# kl25_1.net
KiCad netlist of a schematic drawn in Altium Designer
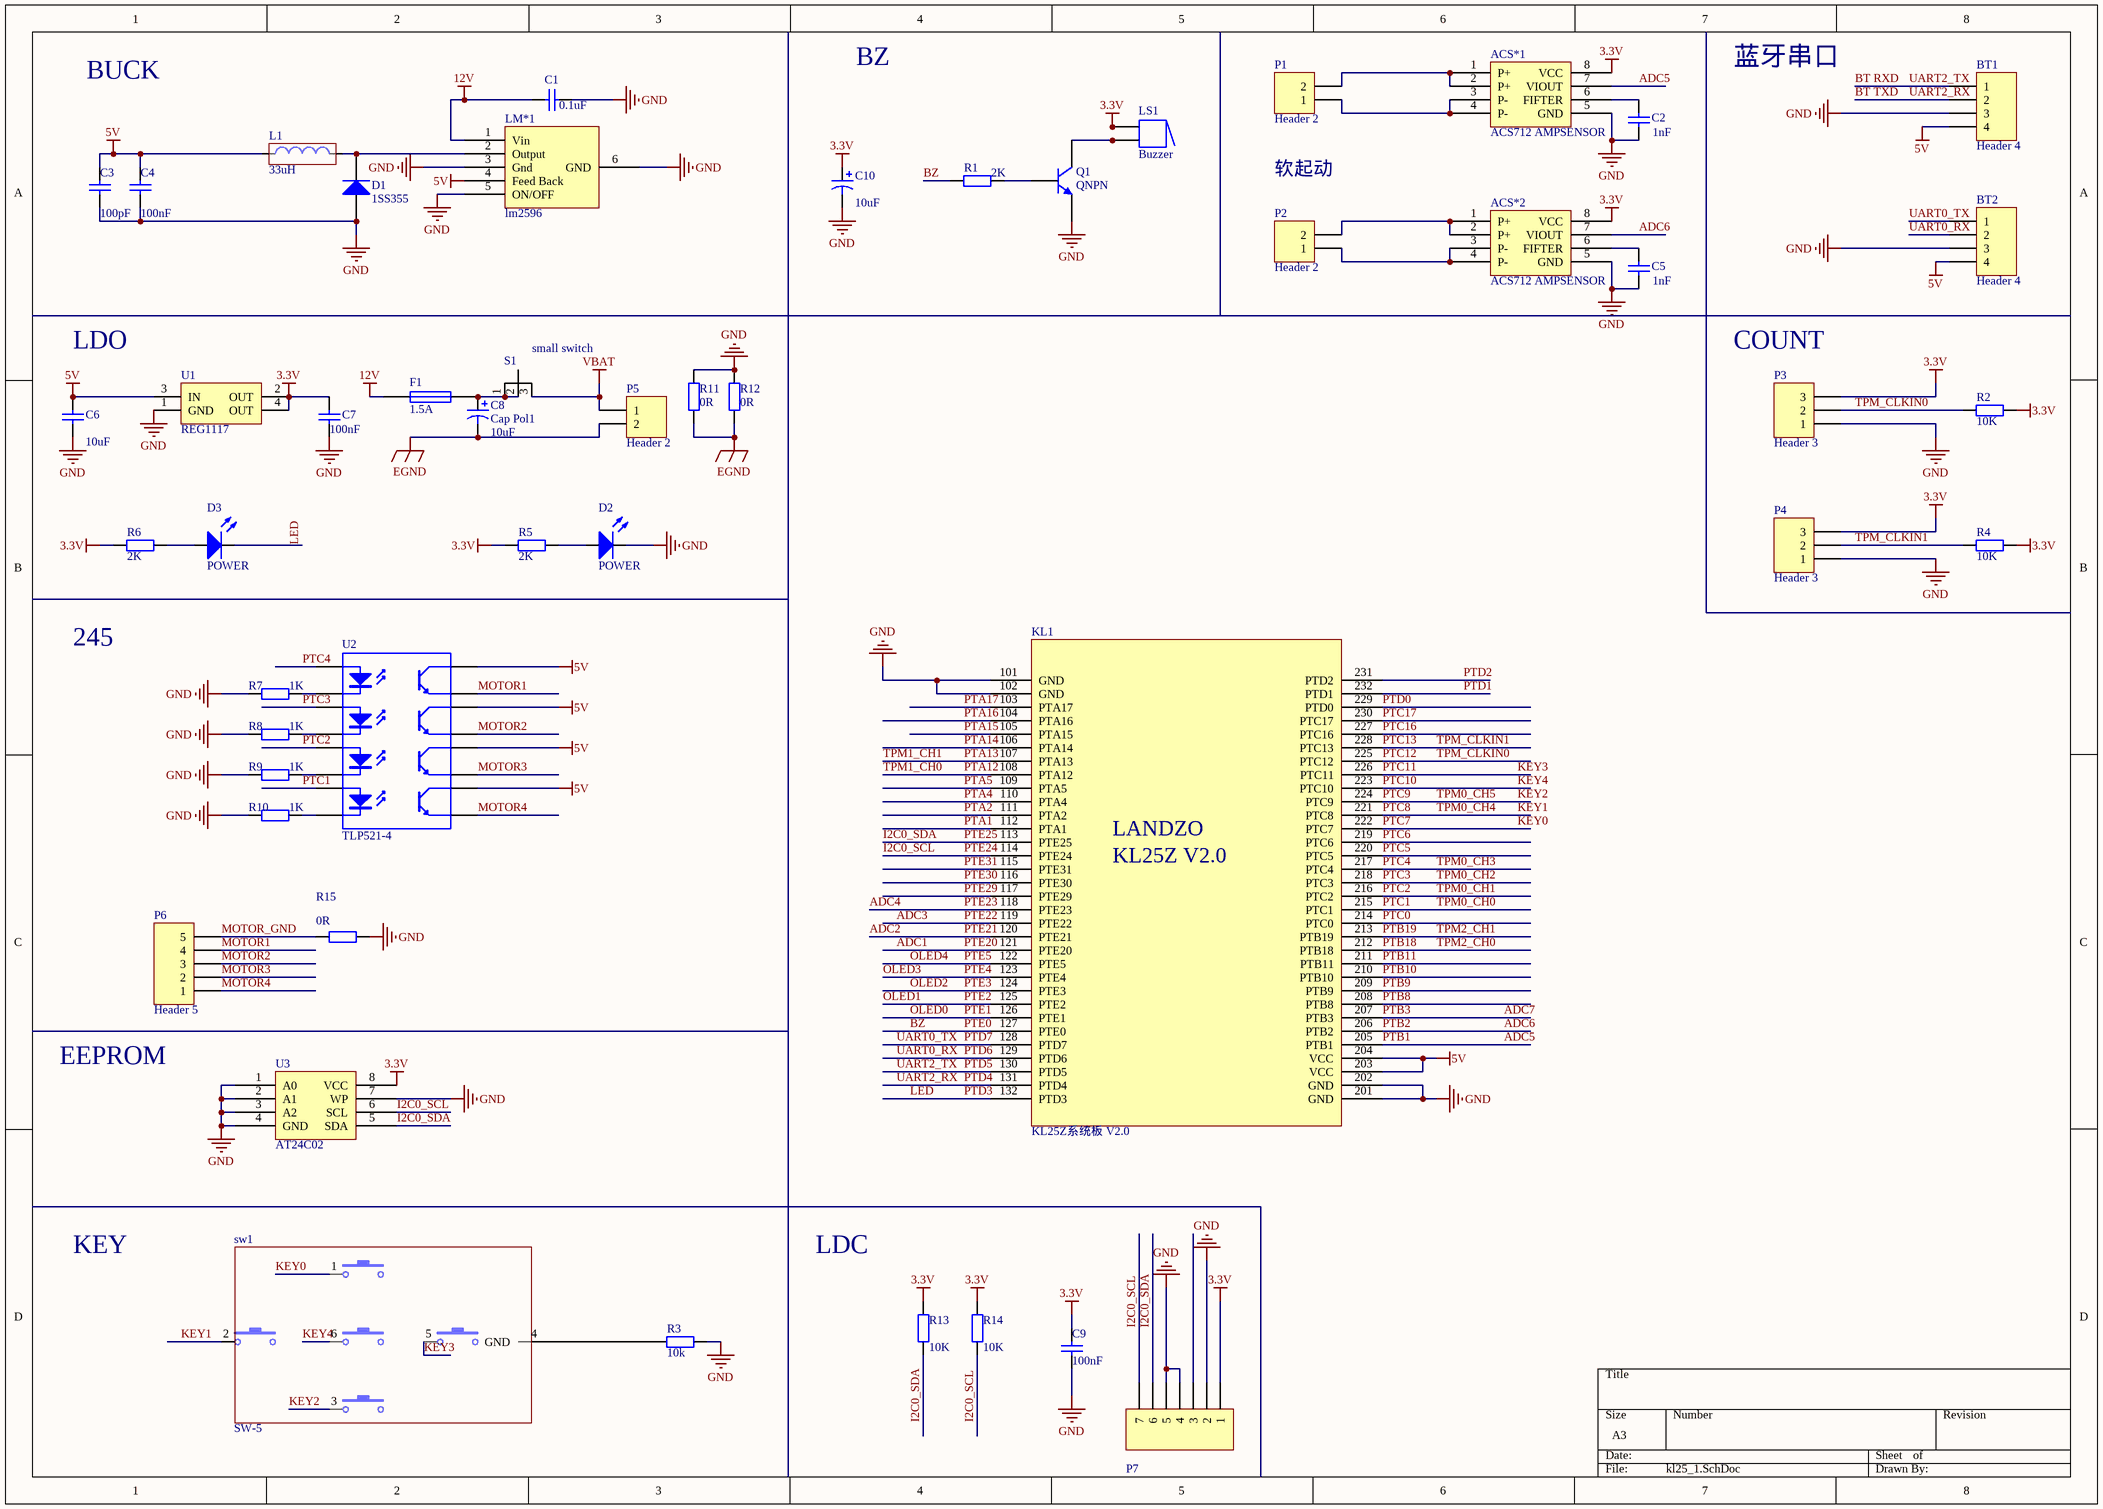
[diagram p0: kl25_1.SchDoc]

(export (version "E")
  (design (tool "Eeschema 10.0.6"))
  (components
    (comp (ref "ACS*1")
      (value "ACS712 AMPSENSOR")
      (footprint "SOIC1-8N ACS712")
      (libsource (lib "2号库") (part "ACS712 AMPSENSOR"))
    )
    (comp (ref "ACS*2")
      (value "ACS712 AMPSENSOR")
      (footprint "SOIC1-8N ACS712")
      (libsource (lib "2号库") (part "ACS712 AMPSENSOR"))
    )
    (comp (ref "BT1")
      (value "Header 4")
      (footprint "HDR1X4")
      (description "Header, 4-Pin")
      (fields (field (name "PUBLISHER") "Altium Limited"))
      (libsource (lib "Sparks") (part "Header 4"))
    )
    (comp (ref "BT2")
      (value "Header 4")
      (footprint "HDR1X4")
      (description "Header, 4-Pin")
      (fields (field (name "PUBLISHER") "Altium Limited"))
      (libsource (lib "Sparks") (part "Header 4"))
    )
    (comp (ref "C1")
      (value "0.1uF")
      (footprint "C2012")
      (description "Capacitor")
      (fields (field (name "Comment") "Cap") (field (name "PUBLISHER") "Altium Limited"))
      (libsource (lib "Miscellaneous Devices") (part "Cap"))
    )
    (comp (ref "C2")
      (value "1nF")
      (footprint "C2012")
      (description "贴片电容")
      (fields (field (name "Comment") "Cap") (field (name "PUBLISHER") "Altium Limited"))
      (libsource (lib "Sparks") (part "Cap"))
    )
    (comp (ref "C3")
      (value "100pF")
      (footprint "C2012")
      (description "Capacitor")
      (fields (field (name "Comment") "Cap") (field (name "PUBLISHER") "Altium Limited"))
      (libsource (lib "Miscellaneous Devices") (part "Cap"))
    )
    (comp (ref "C4")
      (value "100nF")
      (footprint "C2012")
      (description "Capacitor")
      (fields (field (name "Comment") "Cap") (field (name "PUBLISHER") "Altium Limited"))
      (libsource (lib "Miscellaneous Devices") (part "Cap"))
    )
    (comp (ref "C5")
      (value "1nF")
      (footprint "C2012")
      (description "贴片电容")
      (fields (field (name "Comment") "Cap") (field (name "PUBLISHER") "Altium Limited"))
      (libsource (lib "Sparks") (part "Cap"))
    )
    (comp (ref "C6")
      (value "10uF")
      (footprint "C2012")
      (description "贴片电容")
      (fields (field (name "Comment") "Cap") (field (name "PUBLISHER") "Altium Limited"))
      (libsource (lib "Sparks") (part "Cap"))
    )
    (comp (ref "C7")
      (value "100nF")
      (footprint "C2012")
      (description "贴片电容")
      (fields (field (name "Comment") "Cap") (field (name "PUBLISHER") "Altium Limited"))
      (libsource (lib "Sparks") (part "Cap"))
    )
    (comp (ref "C8")
      (value "Cap Pol1")
      (footprint "SMD-EC-F8")
      (description "Polarized Capacitor (Radial)")
      (fields (field (name "ALTIUM_VALUE") "10uF") (field (name "PUBLISHER") "Altium Limited"))
      (libsource (lib "Miscellaneous Devices") (part "Cap Pol1"))
    )
    (comp (ref "C9")
      (value "100nF")
      (footprint "C2012")
      (description "Capacitor")
      (libsource (lib "K60-V4.0") (part "Cap"))
    )
    (comp (ref "C10")
      (value "10uF")
      (footprint "1206(2)")
      (description "Polarized Capacitor (Radial)")
      (fields (field (name "Comment") "Cap Pol1") (field (name "PUBLISHER") "Altium Limited"))
      (libsource (lib "Miscellaneous Devices") (part "Cap Pol1"))
    )
    (comp (ref "D1")
      (value "1SS355")
      (footprint "SK54")
      (description "High Conductance Fast Diode")
      (fields (field (name "PUBLISHER") "Altium Limited"))
      (libsource (lib "K60-V4.0") (part "Diode 1N4148"))
    )
    (comp (ref "D2")
      (value "POWER")
      (footprint "R2012")
      (description "Typical INFRARED GaAs LED")
      (libsource (lib "K60-V4.0") (part "LED"))
    )
    (comp (ref "D3")
      (value "POWER")
      (footprint "R2012")
      (description "Typical INFRARED GaAs LED")
      (libsource (lib "K60-V4.0") (part "LED"))
    )
    (comp (ref "F1")
      (value "1.5A")
      (footprint "1206(2)")
      (description "Fuse")
      (fields (field (name "PUBLISHER") "Altium Limited"))
      (libsource (lib "K60-V4.0") (part "Fuse 1"))
    )
    (comp (ref "KL1")
      (value "KL25Z系统板 V2.0")
      (footprint "KL25 V2.0系统板")
      (libsource (lib "2号库") (part "KL25Z系统板 V2.0"))
    )
    (comp (ref "L1")
      (value "33uH")
      (footprint "SMD-EC-F8")
      (description "Inductor")
      (libsource (lib "Landzo") (part "Inductor"))
    )
    (comp (ref "LM*1") (value "lm2596") (footprint "lm2596") (libsource (lib "2号库") (part "lm2596")))
    (comp (ref "LS1")
      (value "Buzzer")
      (footprint "ABSM-1574")
      (description "Magnetic Transducer Buzzer")
      (fields (field (name "PUBLISHER") "Altium Limited"))
      (libsource (lib "Miscellaneous Devices") (part "Buzzer"))
    )
    (comp (ref "P1")
      (value "Header 2")
      (footprint "HDR1X2")
      (description "Header, 2-Pin")
      (fields (field (name "PUBLISHER") "Altium Limited"))
      (libsource (lib "Sparks") (part "Header 2"))
    )
    (comp (ref "P2")
      (value "Header 2")
      (footprint "HDR1X2")
      (description "Header, 2-Pin")
      (fields (field (name "PUBLISHER") "Altium Limited"))
      (libsource (lib "Sparks") (part "Header 2"))
    )
    (comp (ref "P3")
      (value "Header 3")
      (footprint "HDR1X3")
      (description "Header, 3-Pin")
      (fields (field (name "PUBLISHER") "Altium Limited"))
      (libsource (lib "Sparks") (part "Header 3"))
    )
    (comp (ref "P4")
      (value "Header 3")
      (footprint "HDR1X3")
      (description "Header, 3-Pin")
      (fields (field (name "PUBLISHER") "Altium Limited"))
      (libsource (lib "Sparks") (part "Header 3"))
    )
    (comp (ref "P5")
      (value "Header 2")
      (footprint "HDR1X2")
      (description "Header, 2-Pin")
      (fields (field (name "PUBLISHER") "Altium Limited"))
      (libsource (lib "") (part "Header 2_1"))
    )
    (comp (ref "P6")
      (value "Header 5")
      (footprint "HDR1X5")
      (description "Header, 5-Pin")
      (fields (field (name "PUBLISHER") "Altium Limited"))
      (libsource (lib "Sparks") (part "Header 5"))
    )
    (comp (ref "P7")
      (value "Header 7")
      (footprint "HDR1X7")
      (description "Header, 7-Pin")
      (fields (field (name "PUBLISHER") "Altium Limited"))
      (libsource (lib "Sparks") (part "Header 7"))
    )
    (comp (ref "Q1")
      (value "QNPN")
      (footprint "SOT23_N")
      (description "NPN Bipolar Transistor")
      (fields (field (name "PUBLISHER") "Altium Limited"))
      (libsource (lib "Miscellaneous Devices") (part "QNPN"))
    )
    (comp (ref "R1")
      (value "2K")
      (footprint "R2012")
      (description "Resistor")
      (fields (field (name "Comment") "Res2") (field (name "PUBLISHER") "Altium Limited"))
      (libsource (lib "Miscellaneous Devices") (part "Res2"))
    )
    (comp (ref "R2")
      (value "10K")
      (footprint "R2012")
      (description "Resistor")
      (fields (field (name "Comment") "Res2") (field (name "PUBLISHER") "Altium Limited"))
      (libsource (lib "Miscellaneous Devices") (part "Res2"))
    )
    (comp (ref "R3")
      (value "10k")
      (footprint "R2012")
      (description "Resistor of led")
      (libsource (lib "K60-V4.0") (part "Res"))
    )
    (comp (ref "R4")
      (value "10K")
      (footprint "R2012")
      (description "Resistor")
      (fields (field (name "Comment") "Res2") (field (name "PUBLISHER") "Altium Limited"))
      (libsource (lib "Miscellaneous Devices") (part "Res2"))
    )
    (comp (ref "R5")
      (value "2K")
      (footprint "R2012")
      (description "Resistor")
      (libsource (lib "K60-V4.0") (part "Res"))
    )
    (comp (ref "R6")
      (value "2K")
      (footprint "R2012")
      (description "Resistor")
      (libsource (lib "K60-V4.0") (part "Res"))
    )
    (comp (ref "R7")
      (value "1K")
      (footprint "R2012")
      (description "Resistor")
      (fields (field (name "Comment") "Res2") (field (name "PUBLISHER") "Altium Limited"))
      (libsource (lib "Miscellaneous Devices") (part "Res2"))
    )
    (comp (ref "R8")
      (value "1K")
      (footprint "R2012")
      (description "Resistor")
      (fields (field (name "Comment") "Res2") (field (name "PUBLISHER") "Altium Limited"))
      (libsource (lib "Miscellaneous Devices") (part "Res2"))
    )
    (comp (ref "R9")
      (value "1K")
      (footprint "R2012")
      (description "Resistor")
      (fields (field (name "Comment") "Res2") (field (name "PUBLISHER") "Altium Limited"))
      (libsource (lib "Miscellaneous Devices") (part "Res2"))
    )
    (comp (ref "R10")
      (value "1K")
      (footprint "R2012")
      (description "Resistor")
      (fields (field (name "Comment") "Res2") (field (name "PUBLISHER") "Altium Limited"))
      (libsource (lib "Miscellaneous Devices") (part "Res2"))
    )
    (comp (ref "R11")
      (value "0R")
      (footprint "1206(2)")
      (description "Resistor")
      (fields (field (name "Comment") "Res2") (field (name "PUBLISHER") "Altium Limited"))
      (libsource (lib "") (part "Res2_2"))
    )
    (comp (ref "R12")
      (value "0R")
      (footprint "1206(2)")
      (description "Resistor")
      (fields (field (name "Comment") "Res2") (field (name "PUBLISHER") "Altium Limited"))
      (libsource (lib "") (part "Res2_2"))
    )
    (comp (ref "R13")
      (value "10K")
      (footprint "R2012")
      (description "Resistor")
      (fields (field (name "Comment") "Res2") (field (name "PUBLISHER") "Altium Limited"))
      (libsource (lib "") (part "Res2_1"))
    )
    (comp (ref "R14")
      (value "10K")
      (footprint "R2012")
      (description "Resistor")
      (fields (field (name "Comment") "Res2") (field (name "PUBLISHER") "Altium Limited"))
      (libsource (lib "") (part "Res2_1"))
    )
    (comp (ref "R15")
      (value "0R")
      (footprint "1206(2)")
      (description "Resistor")
      (fields (field (name "Comment") "Res2") (field (name "PUBLISHER") "Altium Limited"))
      (libsource (lib "Miscellaneous Devices") (part "Res2"))
    )
    (comp (ref "S1")
      (value "small switch")
      (footprint "small switch")
      (libsource (lib "2号库") (part "small switch"))
    )
    (comp (ref "sw1") (value "SW-5") (footprint "SW-5") (libsource (lib "2号库") (part "SW-5")))
    (comp (ref "U1")
      (value "REG1117")
      (footprint "SOT223")
      (description "800mA and 1A Low Dropout Positive Regulator 2.85V, 3.3V, 5V, and Adjustable")
      (fields (field (name "PUBLISHER") "Altium Limited"))
      (libsource (lib "Sparks") (part "REG1117"))
    )
    (comp (ref "U2") (value "TLP521-4") (footprint "DIP-16") (libsource (lib "原理图") (part "TLP521-4")))
    (comp (ref "U3") (value "AT24C02") (footprint "IR2104") (libsource (lib "2号库") (part "AT24C02")))
  )
  (nets
    (net (code "1") (name "/ADC1") (class "Default")
      (node (ref "KL1") (pin "121") (pinfunction "PTE20_121") (pintype "passive"))
    )
    (net (code "2") (name "/ADC2") (class "Default")
      (node (ref "KL1") (pin "120") (pinfunction "PTE21_120") (pintype "passive"))
    )
    (net (code "3") (name "/ADC3") (class "Default")
      (node (ref "KL1") (pin "119") (pinfunction "PTE22_119") (pintype "passive"))
    )
    (net (code "4") (name "/ADC4") (class "Default")
      (node (ref "KL1") (pin "118") (pinfunction "PTE23_118") (pintype "passive"))
    )
    (net (code "5") (name "/ADC5") (class "Default")
      (node (ref "ACS*1") (pin "7") (pinfunction "VIOUT_7") (pintype "passive"))
      (node (ref "KL1") (pin "205") (pinfunction "PTB1_205") (pintype "passive"))
    )
    (net (code "6") (name "/ADC6") (class "Default")
      (node (ref "ACS*2") (pin "7") (pinfunction "VIOUT_7") (pintype "passive"))
      (node (ref "KL1") (pin "206") (pinfunction "PTB2_206") (pintype "passive"))
    )
    (net (code "7") (name "/ADC7") (class "Default")
      (node (ref "KL1") (pin "207") (pinfunction "PTB3_207") (pintype "passive"))
    )
    (net (code "8") (name "/BT RXD") (class "Default")
      (node (ref "BT1") (pin "1") (pinfunction "1_1") (pintype "passive"))
      (node (ref "KL1") (pin "130") (pinfunction "PTD5_130") (pintype "passive"))
    )
    (net (code "9") (name "/BT TXD") (class "Default")
      (node (ref "BT1") (pin "2") (pinfunction "2_2") (pintype "passive"))
      (node (ref "KL1") (pin "131") (pinfunction "PTD4_131") (pintype "passive"))
    )
    (net (code "10") (name "/BZ") (class "Default")
      (node (ref "KL1") (pin "127") (pinfunction "PTE0_127") (pintype "passive"))
      (node (ref "R1") (pin "2") (pinfunction "2_2") (pintype "passive"))
    )
    (net (code "11") (name "/I2C0_SCL") (class "Default")
      (node (ref "KL1") (pin "114") (pinfunction "PTE24_114") (pintype "passive"))
      (node (ref "P7") (pin "7") (pinfunction "7_7") (pintype "passive"))
      (node (ref "R14") (pin "1") (pinfunction "1_1") (pintype "passive"))
      (node (ref "U3") (pin "6") (pinfunction "SCL_6") (pintype "passive"))
    )
    (net (code "12") (name "/I2C0_SDA") (class "Default")
      (node (ref "KL1") (pin "113") (pinfunction "PTE25_113") (pintype "passive"))
      (node (ref "P7") (pin "6") (pinfunction "6_6") (pintype "passive"))
      (node (ref "R13") (pin "1") (pinfunction "1_1") (pintype "passive"))
      (node (ref "U3") (pin "5") (pinfunction "SDA_5") (pintype "passive"))
    )
    (net (code "13") (name "/KEY0") (class "Default")
      (node (ref "KL1") (pin "222") (pinfunction "PTC7_222") (pintype "passive"))
      (node (ref "sw1") (pin "1") (pinfunction "1_1") (pintype "passive"))
    )
    (net (code "14") (name "/KEY1") (class "Default")
      (node (ref "KL1") (pin "221") (pinfunction "PTC8_221") (pintype "passive"))
      (node (ref "sw1") (pin "2") (pinfunction "2_2") (pintype "passive"))
    )
    (net (code "15") (name "/KEY2") (class "Default")
      (node (ref "KL1") (pin "224") (pinfunction "PTC9_224") (pintype "passive"))
      (node (ref "sw1") (pin "3") (pinfunction "3_3") (pintype "passive"))
    )
    (net (code "16") (name "/KEY3") (class "Default")
      (node (ref "KL1") (pin "226") (pinfunction "PTC11_226") (pintype "passive"))
      (node (ref "sw1") (pin "5") (pinfunction "5_5") (pintype "passive"))
    )
    (net (code "17") (name "/KEY4") (class "Default")
      (node (ref "KL1") (pin "223") (pinfunction "PTC10_223") (pintype "passive"))
      (node (ref "sw1") (pin "6") (pinfunction "6_6") (pintype "passive"))
    )
    (net (code "18") (name "/LED") (class "Default")
      (node (ref "D3") (pin "2") (pinfunction "2_2") (pintype "passive"))
      (node (ref "KL1") (pin "132") (pinfunction "PTD3_132") (pintype "passive"))
    )
    (net (code "19") (name "/MOTOR1") (class "Default")
      (node (ref "P6") (pin "4") (pinfunction "4_4") (pintype "passive"))
      (node (ref "U2") (pin "15") (pinfunction "15_15") (pintype "passive"))
    )
    (net (code "20") (name "/MOTOR2") (class "Default")
      (node (ref "P6") (pin "3") (pinfunction "3_3") (pintype "passive"))
      (node (ref "U2") (pin "13") (pinfunction "13_13") (pintype "passive"))
    )
    (net (code "21") (name "/MOTOR3") (class "Default")
      (node (ref "P6") (pin "2") (pinfunction "2_2") (pintype "passive"))
      (node (ref "U2") (pin "11") (pinfunction "11_11") (pintype "passive"))
    )
    (net (code "22") (name "/MOTOR4") (class "Default")
      (node (ref "P6") (pin "1") (pinfunction "1_1") (pintype "passive"))
      (node (ref "U2") (pin "9") (pinfunction "9_9") (pintype "passive"))
    )
    (net (code "23") (name "/MOTOR_GND") (class "Default")
      (node (ref "P6") (pin "5") (pinfunction "5_5") (pintype "passive"))
      (node (ref "R15") (pin "2") (pinfunction "2_2") (pintype "passive"))
    )
    (net (code "24") (name "/OLED0") (class "Default")
      (node (ref "KL1") (pin "126") (pinfunction "PTE1_126") (pintype "passive"))
    )
    (net (code "25") (name "/OLED1") (class "Default")
      (node (ref "KL1") (pin "125") (pinfunction "PTE2_125") (pintype "passive"))
    )
    (net (code "26") (name "/OLED2") (class "Default")
      (node (ref "KL1") (pin "124") (pinfunction "PTE3_124") (pintype "passive"))
    )
    (net (code "27") (name "/OLED3") (class "Default")
      (node (ref "KL1") (pin "123") (pinfunction "PTE4_123") (pintype "passive"))
    )
    (net (code "28") (name "/OLED4") (class "Default")
      (node (ref "KL1") (pin "122") (pinfunction "PTE5_122") (pintype "passive"))
    )
    (net (code "29") (name "/PTA1") (class "Default")
      (node (ref "KL1") (pin "112") (pinfunction "PTA1_112") (pintype "passive"))
    )
    (net (code "30") (name "/PTA2") (class "Default")
      (node (ref "KL1") (pin "111") (pinfunction "PTA2_111") (pintype "passive"))
    )
    (net (code "31") (name "/PTA4") (class "Default")
      (node (ref "KL1") (pin "110") (pinfunction "PTA4_110") (pintype "passive"))
    )
    (net (code "32") (name "/PTA5") (class "Default")
      (node (ref "KL1") (pin "109") (pinfunction "PTA5_109") (pintype "passive"))
    )
    (net (code "33") (name "/PTA12") (class "Default")
      (node (ref "KL1") (pin "108") (pinfunction "PTA12_108") (pintype "passive"))
    )
    (net (code "34") (name "/PTA13") (class "Default")
      (node (ref "KL1") (pin "107") (pinfunction "PTA13_107") (pintype "passive"))
    )
    (net (code "35") (name "/PTA14") (class "Default")
      (node (ref "KL1") (pin "106") (pinfunction "PTA14_106") (pintype "passive"))
    )
    (net (code "36") (name "/PTA15") (class "Default")
      (node (ref "KL1") (pin "105") (pinfunction "PTA15_105") (pintype "passive"))
    )
    (net (code "37") (name "/PTA16") (class "Default")
      (node (ref "KL1") (pin "104") (pinfunction "PTA16_104") (pintype "passive"))
    )
    (net (code "38") (name "/PTA17") (class "Default")
      (node (ref "KL1") (pin "103") (pinfunction "PTA17_103") (pintype "passive"))
    )
    (net (code "39") (name "/PTB8") (class "Default")
      (node (ref "KL1") (pin "208") (pinfunction "PTB8_208") (pintype "passive"))
    )
    (net (code "40") (name "/PTB9") (class "Default")
      (node (ref "KL1") (pin "209") (pinfunction "PTB9_209") (pintype "passive"))
    )
    (net (code "41") (name "/PTB10") (class "Default")
      (node (ref "KL1") (pin "210") (pinfunction "PTB10_210") (pintype "passive"))
    )
    (net (code "42") (name "/PTB11") (class "Default")
      (node (ref "KL1") (pin "211") (pinfunction "PTB11_211") (pintype "passive"))
    )
    (net (code "43") (name "/PTB18") (class "Default")
      (node (ref "KL1") (pin "212") (pinfunction "PTB18_212") (pintype "passive"))
    )
    (net (code "44") (name "/PTB19") (class "Default")
      (node (ref "KL1") (pin "213") (pinfunction "PTB19_213") (pintype "passive"))
    )
    (net (code "45") (name "/PTC0") (class "Default")
      (node (ref "KL1") (pin "214") (pinfunction "PTC0_214") (pintype "passive"))
    )
    (net (code "46") (name "/PTC1") (class "Default")
      (node (ref "KL1") (pin "215") (pinfunction "PTC1_215") (pintype "passive"))
      (node (ref "U2") (pin "7") (pinfunction "7_7") (pintype "passive"))
    )
    (net (code "47") (name "/PTC2") (class "Default")
      (node (ref "KL1") (pin "216") (pinfunction "PTC2_216") (pintype "passive"))
      (node (ref "U2") (pin "5") (pinfunction "5_5") (pintype "passive"))
    )
    (net (code "48") (name "/PTC3") (class "Default")
      (node (ref "KL1") (pin "218") (pinfunction "PTC3_218") (pintype "passive"))
      (node (ref "U2") (pin "3") (pinfunction "3_3") (pintype "passive"))
    )
    (net (code "49") (name "/PTC4") (class "Default")
      (node (ref "KL1") (pin "217") (pinfunction "PTC4_217") (pintype "passive"))
      (node (ref "U2") (pin "1") (pinfunction "1_1") (pintype "passive"))
    )
    (net (code "50") (name "/PTC5") (class "Default")
      (node (ref "KL1") (pin "220") (pinfunction "PTC5_220") (pintype "passive"))
    )
    (net (code "51") (name "/PTC6") (class "Default")
      (node (ref "KL1") (pin "219") (pinfunction "PTC6_219") (pintype "passive"))
    )
    (net (code "52") (name "/PTC12") (class "Default")
      (node (ref "KL1") (pin "225") (pinfunction "PTC12_225") (pintype "passive"))
      (node (ref "P3") (pin "2") (pinfunction "2_2") (pintype "passive"))
      (node (ref "R2") (pin "2") (pinfunction "2_2") (pintype "passive"))
    )
    (net (code "53") (name "/PTC13") (class "Default")
      (node (ref "KL1") (pin "228") (pinfunction "PTC13_228") (pintype "passive"))
      (node (ref "P4") (pin "2") (pinfunction "2_2") (pintype "passive"))
      (node (ref "R4") (pin "2") (pinfunction "2_2") (pintype "passive"))
    )
    (net (code "54") (name "/PTC16") (class "Default")
      (node (ref "KL1") (pin "227") (pinfunction "PTC16_227") (pintype "passive"))
    )
    (net (code "55") (name "/PTC17") (class "Default")
      (node (ref "KL1") (pin "230") (pinfunction "PTC17_230") (pintype "passive"))
    )
    (net (code "56") (name "/PTD0") (class "Default")
      (node (ref "KL1") (pin "229") (pinfunction "PTD0_229") (pintype "passive"))
    )
    (net (code "57") (name "/PTD1") (class "Default")
      (node (ref "KL1") (pin "232") (pinfunction "PTD1_232") (pintype "passive"))
    )
    (net (code "58") (name "/PTD2") (class "Default")
      (node (ref "KL1") (pin "231") (pinfunction "PTD2_231") (pintype "passive"))
    )
    (net (code "59") (name "/PTD6") (class "Default")
      (node (ref "BT2") (pin "2") (pinfunction "2_2") (pintype "passive"))
      (node (ref "KL1") (pin "129") (pinfunction "PTD6_129") (pintype "passive"))
    )
    (net (code "60") (name "/PTD7") (class "Default")
      (node (ref "BT2") (pin "1") (pinfunction "1_1") (pintype "passive"))
      (node (ref "KL1") (pin "128") (pinfunction "PTD7_128") (pintype "passive"))
    )
    (net (code "61") (name "/PTE29") (class "Default")
      (node (ref "KL1") (pin "117") (pinfunction "PTE29_117") (pintype "passive"))
    )
    (net (code "62") (name "/PTE30") (class "Default")
      (node (ref "KL1") (pin "116") (pinfunction "PTE30_116") (pintype "passive"))
    )
    (net (code "63") (name "/PTE31") (class "Default")
      (node (ref "KL1") (pin "115") (pinfunction "PTE31_115") (pintype "passive"))
    )
    (net (code "64") (name "3.3V") (class "Default")
      (node (ref "ACS*1") (pin "8") (pinfunction "VCC_8") (pintype "passive"))
      (node (ref "ACS*2") (pin "8") (pinfunction "VCC_8") (pintype "passive"))
      (node (ref "C10") (pin "1") (pinfunction "1_1") (pintype "passive"))
      (node (ref "C7") (pin "2") (pinfunction "2_2") (pintype "passive"))
      (node (ref "C9") (pin "2") (pinfunction "2_2") (pintype "passive"))
      (node (ref "LS1") (pin "1") (pinfunction "1_1") (pintype "passive"))
      (node (ref "LS1") (pin "1A") (pinfunction "1A_1A") (pintype "passive"))
      (node (ref "P3") (pin "3") (pinfunction "3_3") (pintype "passive"))
      (node (ref "P4") (pin "3") (pinfunction "3_3") (pintype "passive"))
      (node (ref "P7") (pin "1") (pinfunction "1_1") (pintype "passive"))
      (node (ref "R13") (pin "2") (pinfunction "2_2") (pintype "passive"))
      (node (ref "R14") (pin "2") (pinfunction "2_2") (pintype "passive"))
      (node (ref "R2") (pin "1") (pinfunction "1_1") (pintype "passive"))
      (node (ref "R4") (pin "1") (pinfunction "1_1") (pintype "passive"))
      (node (ref "R5") (pin "2") (pinfunction "2_2") (pintype "passive"))
      (node (ref "R6") (pin "2") (pinfunction "2_2") (pintype "passive"))
      (node (ref "U1") (pin "2") (pinfunction "OUT_2") (pintype "power_in"))
      (node (ref "U1") (pin "4") (pinfunction "OUT_4") (pintype "power_in"))
      (node (ref "U3") (pin "8") (pinfunction "VCC_8") (pintype "passive"))
    )
    (net (code "65") (name "5V") (class "Default")
      (node (ref "BT1") (pin "4") (pinfunction "4_4") (pintype "passive"))
      (node (ref "BT2") (pin "4") (pinfunction "4_4") (pintype "passive"))
      (node (ref "C3") (pin "2") (pinfunction "2_2") (pintype "passive"))
      (node (ref "C4") (pin "2") (pinfunction "2_2") (pintype "passive"))
      (node (ref "C6") (pin "2") (pinfunction "2_2") (pintype "passive"))
      (node (ref "KL1") (pin "203") (pinfunction "VCC_203") (pintype "passive"))
      (node (ref "KL1") (pin "204") (pinfunction "VCC_204") (pintype "passive"))
      (node (ref "L1") (pin "1") (pinfunction "1_1") (pintype "passive"))
      (node (ref "LM*1") (pin "4") (pinfunction "Feed_Back_4") (pintype "passive"))
      (node (ref "U1") (pin "3") (pinfunction "IN_3") (pintype "power_in"))
      (node (ref "U2") (pin "10") (pinfunction "10_10") (pintype "passive"))
      (node (ref "U2") (pin "12") (pinfunction "12_12") (pintype "passive"))
      (node (ref "U2") (pin "14") (pinfunction "14_14") (pintype "passive"))
      (node (ref "U2") (pin "16") (pinfunction "16_16") (pintype "passive"))
    )
    (net (code "66") (name "12V") (class "Default")
      (node (ref "C1") (pin "2") (pinfunction "2_2") (pintype "passive"))
      (node (ref "F1") (pin "1") (pinfunction "1_1") (pintype "passive"))
      (node (ref "LM*1") (pin "1") (pinfunction "Vin_1") (pintype "passive"))
    )
    (net (code "67") (name "EGND") (class "Default")
      (node (ref "C8") (pin "2") (pinfunction "2_2") (pintype "passive"))
      (node (ref "P5") (pin "2") (pinfunction "2_2") (pintype "passive"))
      (node (ref "R11") (pin "2") (pinfunction "2_2") (pintype "passive"))
      (node (ref "R12") (pin "2") (pinfunction "2_2") (pintype "passive"))
    )
    (net (code "68") (name "GND") (class "Default")
      (node (ref "ACS*1") (pin "5") (pinfunction "GND_5") (pintype "passive"))
      (node (ref "ACS*2") (pin "5") (pinfunction "GND_5") (pintype "passive"))
      (node (ref "BT1") (pin "3") (pinfunction "3_3") (pintype "passive"))
      (node (ref "BT2") (pin "3") (pinfunction "3_3") (pintype "passive"))
      (node (ref "C1") (pin "1") (pinfunction "1_1") (pintype "passive"))
      (node (ref "C10") (pin "2") (pinfunction "2_2") (pintype "passive"))
      (node (ref "C2") (pin "1") (pinfunction "1_1") (pintype "passive"))
      (node (ref "C3") (pin "1") (pinfunction "1_1") (pintype "passive"))
      (node (ref "C4") (pin "1") (pinfunction "1_1") (pintype "passive"))
      (node (ref "C5") (pin "1") (pinfunction "1_1") (pintype "passive"))
      (node (ref "C6") (pin "1") (pinfunction "1_1") (pintype "passive"))
      (node (ref "C7") (pin "1") (pinfunction "1_1") (pintype "passive"))
      (node (ref "C9") (pin "1") (pinfunction "1_1") (pintype "passive"))
      (node (ref "D1") (pin "1") (pinfunction "A_1") (pintype "passive"))
      (node (ref "D2") (pin "2") (pinfunction "2_2") (pintype "passive"))
      (node (ref "KL1") (pin "101") (pinfunction "GND_101") (pintype "passive"))
      (node (ref "KL1") (pin "102") (pinfunction "GND_102") (pintype "passive"))
      (node (ref "KL1") (pin "201") (pinfunction "GND_201") (pintype "passive"))
      (node (ref "KL1") (pin "202") (pinfunction "GND_202") (pintype "passive"))
      (node (ref "LM*1") (pin "3") (pinfunction "Gnd_3") (pintype "passive"))
      (node (ref "LM*1") (pin "5") (pinfunction "ON/OFF_5") (pintype "passive"))
      (node (ref "LM*1") (pin "6") (pinfunction "GND_6") (pintype "passive"))
      (node (ref "P3") (pin "1") (pinfunction "1_1") (pintype "passive"))
      (node (ref "P4") (pin "1") (pinfunction "1_1") (pintype "passive"))
      (node (ref "P7") (pin "2") (pinfunction "2_2") (pintype "passive"))
      (node (ref "P7") (pin "4") (pinfunction "4_4") (pintype "passive"))
      (node (ref "P7") (pin "5") (pinfunction "5_5") (pintype "passive"))
      (node (ref "Q1") (pin "3") (pinfunction "E_3") (pintype "passive"))
      (node (ref "R10") (pin "2") (pinfunction "2_2") (pintype "passive"))
      (node (ref "R11") (pin "1") (pinfunction "1_1") (pintype "passive"))
      (node (ref "R12") (pin "1") (pinfunction "1_1") (pintype "passive"))
      (node (ref "R15") (pin "1") (pinfunction "1_1") (pintype "passive"))
      (node (ref "R3") (pin "1") (pinfunction "1_1") (pintype "passive"))
      (node (ref "R7") (pin "2") (pinfunction "2_2") (pintype "passive"))
      (node (ref "R8") (pin "2") (pinfunction "2_2") (pintype "passive"))
      (node (ref "R9") (pin "2") (pinfunction "2_2") (pintype "passive"))
      (node (ref "U1") (pin "1") (pinfunction "GND_1") (pintype "power_in"))
      (node (ref "U3") (pin "1") (pinfunction "A0_1") (pintype "passive"))
      (node (ref "U3") (pin "2") (pinfunction "A1_2") (pintype "passive"))
      (node (ref "U3") (pin "3") (pinfunction "A2_3") (pintype "passive"))
      (node (ref "U3") (pin "4") (pinfunction "GND_4") (pintype "passive"))
      (node (ref "U3") (pin "7") (pinfunction "WP_7") (pintype "passive"))
    )
    (net (code "69") (name "Net-(ACS*1-FIFTER)") (class "Default")
      (node (ref "ACS*1") (pin "6") (pinfunction "FIFTER_6") (pintype "passive"))
      (node (ref "C2") (pin "2") (pinfunction "2_2") (pintype "passive"))
    )
    (net (code "70") (name "Net-(ACS*1-P+-Pad1)") (class "Default")
      (node (ref "ACS*1") (pin "1") (pinfunction "P+_1") (pintype "passive"))
      (node (ref "ACS*1") (pin "2") (pinfunction "P+_2") (pintype "passive"))
      (node (ref "P1") (pin "2") (pinfunction "2_2") (pintype "passive"))
    )
    (net (code "71") (name "Net-(ACS*1-P--Pad3)") (class "Default")
      (node (ref "ACS*1") (pin "3") (pinfunction "P-_3") (pintype "passive"))
      (node (ref "ACS*1") (pin "4") (pinfunction "P-_4") (pintype "passive"))
      (node (ref "P1") (pin "1") (pinfunction "1_1") (pintype "passive"))
    )
    (net (code "72") (name "Net-(ACS*2-FIFTER)") (class "Default")
      (node (ref "ACS*2") (pin "6") (pinfunction "FIFTER_6") (pintype "passive"))
      (node (ref "C5") (pin "2") (pinfunction "2_2") (pintype "passive"))
    )
    (net (code "73") (name "Net-(ACS*2-P+-Pad1)") (class "Default")
      (node (ref "ACS*2") (pin "1") (pinfunction "P+_1") (pintype "passive"))
      (node (ref "ACS*2") (pin "2") (pinfunction "P+_2") (pintype "passive"))
      (node (ref "P2") (pin "2") (pinfunction "2_2") (pintype "passive"))
    )
    (net (code "74") (name "Net-(ACS*2-P--Pad3)") (class "Default")
      (node (ref "ACS*2") (pin "3") (pinfunction "P-_3") (pintype "passive"))
      (node (ref "ACS*2") (pin "4") (pinfunction "P-_4") (pintype "passive"))
      (node (ref "P2") (pin "1") (pinfunction "1_1") (pintype "passive"))
    )
    (net (code "75") (name "Net-(C8-Pad1)") (class "Default")
      (node (ref "C8") (pin "1") (pinfunction "1_1") (pintype "passive"))
      (node (ref "F1") (pin "2") (pinfunction "2_2") (pintype "passive"))
      (node (ref "S1") (pin "1") (pinfunction "1_1") (pintype "passive"))
      (node (ref "S1") (pin "2") (pinfunction "2_2") (pintype "passive"))
    )
    (net (code "76") (name "Net-(D1-K)") (class "Default")
      (node (ref "D1") (pin "2") (pinfunction "K_2") (pintype "passive"))
      (node (ref "L1") (pin "2") (pinfunction "2_2") (pintype "passive"))
      (node (ref "LM*1") (pin "2") (pinfunction "Output_2") (pintype "passive"))
    )
    (net (code "77") (name "Net-(D2-Pad1)") (class "Default")
      (node (ref "D2") (pin "1") (pinfunction "1_1") (pintype "passive"))
      (node (ref "R5") (pin "1") (pinfunction "1_1") (pintype "passive"))
    )
    (net (code "78") (name "Net-(D3-Pad1)") (class "Default")
      (node (ref "D3") (pin "1") (pinfunction "1_1") (pintype "passive"))
      (node (ref "R6") (pin "1") (pinfunction "1_1") (pintype "passive"))
    )
    (net (code "79") (name "Net-(Q1-B)") (class "Default")
      (node (ref "Q1") (pin "2") (pinfunction "B_2") (pintype "passive"))
      (node (ref "R1") (pin "1") (pinfunction "1_1") (pintype "passive"))
    )
    (net (code "80") (name "Net-(Q1-C)") (class "Default")
      (node (ref "LS1") (pin "2") (pinfunction "2_2") (pintype "passive"))
      (node (ref "LS1") (pin "2A") (pinfunction "2A_2A") (pintype "passive"))
      (node (ref "Q1") (pin "1") (pinfunction "C_1") (pintype "passive"))
    )
    (net (code "81") (name "Net-(R7-Pad1)") (class "Default")
      (node (ref "R7") (pin "1") (pinfunction "1_1") (pintype "passive"))
      (node (ref "U2") (pin "2") (pinfunction "2_2") (pintype "passive"))
    )
    (net (code "82") (name "Net-(R8-Pad1)") (class "Default")
      (node (ref "R8") (pin "1") (pinfunction "1_1") (pintype "passive"))
      (node (ref "U2") (pin "4") (pinfunction "4_4") (pintype "passive"))
    )
    (net (code "83") (name "Net-(R9-Pad1)") (class "Default")
      (node (ref "R9") (pin "1") (pinfunction "1_1") (pintype "passive"))
      (node (ref "U2") (pin "6") (pinfunction "6_6") (pintype "passive"))
    )
    (net (code "84") (name "Net-(R10-Pad1)") (class "Default")
      (node (ref "R10") (pin "1") (pinfunction "1_1") (pintype "passive"))
      (node (ref "U2") (pin "8") (pinfunction "8_8") (pintype "passive"))
    )
    (net (code "85") (name "Net-(sw1-GND)") (class "Default")
      (node (ref "R3") (pin "2") (pinfunction "2_2") (pintype "passive"))
      (node (ref "sw1") (pin "4") (pinfunction "GND_4") (pintype "passive"))
    )
    (net (code "86") (name "VBAT") (class "Default")
      (node (ref "P5") (pin "1") (pinfunction "1_1") (pintype "passive"))
      (node (ref "S1") (pin "3") (pinfunction "3_3") (pintype "passive"))
    )
    (net (code "87") (name "unconnected-(P7-Pad3)") (class "Default")
      (node (ref "P7") (pin "3") (pinfunction "3_3") (pintype "passive"))
    )
  )
)
